# OLED_Adapter.net
KiCad netlist of a schematic drawn in EAGLE
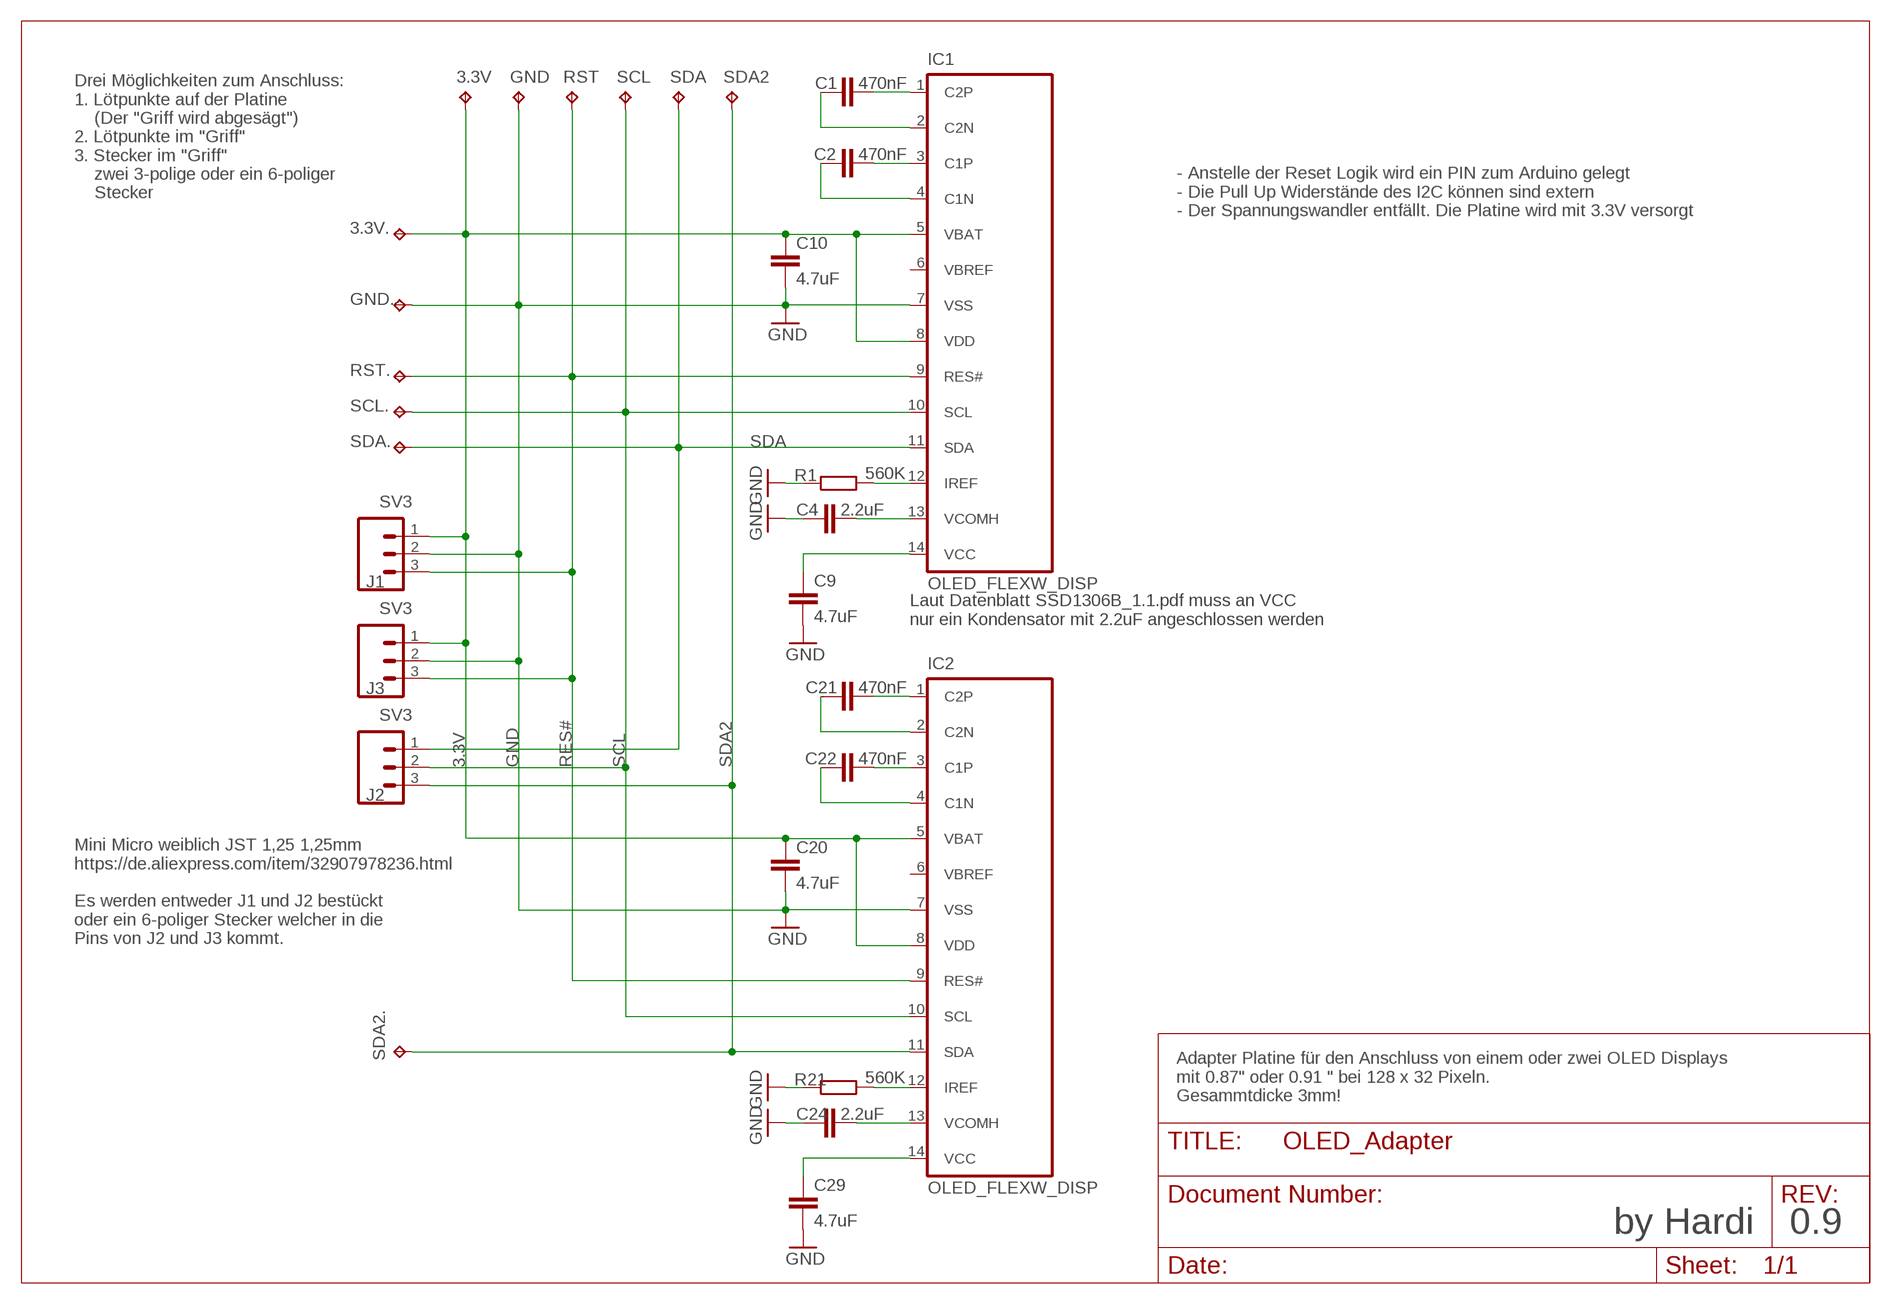
[diagram p0: schematic, sheet 1]

(export (version "E")
  (design (tool "Eeschema 10.0.6"))
  (components
    (comp (ref "3.3V")
      (value "3.3V")
      (footprint "eagle-import:TP16SQ")
      (libsource (lib "eagle-import") (part "TPTP16SQ"))
    )
    (comp (ref "3.3V.")
      (value "TPTP16SQ")
      (footprint "eagle-import:TP16SQ")
      (libsource (lib "eagle-import") (part "TPTP16SQ"))
    )
    (comp (ref "C1")
      (value "470nF")
      (footprint "eagle-import:C0603")
      (libsource (lib "eagle-import") (part "C-EUC0603"))
    )
    (comp (ref "C2")
      (value "470nF")
      (footprint "eagle-import:C0603")
      (libsource (lib "eagle-import") (part "C-EUC0603"))
    )
    (comp (ref "C4")
      (value "2.2uF")
      (footprint "eagle-import:C0603")
      (libsource (lib "eagle-import") (part "C-EUC0603"))
    )
    (comp (ref "C9")
      (value "4.7uF")
      (footprint "eagle-import:C0603")
      (libsource (lib "eagle-import") (part "C-EUC0603"))
    )
    (comp (ref "C10")
      (value "4.7uF")
      (footprint "eagle-import:C0603")
      (libsource (lib "eagle-import") (part "C-EUC0603"))
    )
    (comp (ref "C20")
      (value "4.7uF")
      (footprint "eagle-import:C0603")
      (libsource (lib "eagle-import") (part "C-EUC0603"))
    )
    (comp (ref "C21")
      (value "470nF")
      (footprint "eagle-import:C0603")
      (libsource (lib "eagle-import") (part "C-EUC0603"))
    )
    (comp (ref "C22")
      (value "470nF")
      (footprint "eagle-import:C0603")
      (libsource (lib "eagle-import") (part "C-EUC0603"))
    )
    (comp (ref "C24")
      (value "2.2uF")
      (footprint "eagle-import:C0603")
      (libsource (lib "eagle-import") (part "C-EUC0603"))
    )
    (comp (ref "C29")
      (value "4.7uF")
      (footprint "eagle-import:C0603")
      (libsource (lib "eagle-import") (part "C-EUC0603"))
    )
    (comp (ref "GND")
      (value "GND")
      (footprint "eagle-import:TP16R")
      (libsource (lib "eagle-import") (part "TPTP16R"))
    )
    (comp (ref "GND.")
      (value "TPTP16R")
      (footprint "eagle-import:TP16R")
      (libsource (lib "eagle-import") (part "TPTP16R"))
    )
    (comp (ref "IC1")
      (value "OLED_FLEXW_DISP")
      (footprint "eagle-import:OLED_FLEX_W_DISP")
      (libsource (lib "eagle-import") (part "OLED_FLEXW_DISP"))
    )
    (comp (ref "IC2")
      (value "OLED_FLEXW_DISP")
      (footprint "eagle-import:OLED_FLEX_W_DISP")
      (libsource (lib "eagle-import") (part "OLED_FLEXW_DISP"))
    )
    (comp (ref "J1")
      (value "SV3")
      (footprint "eagle-import:MINI")
      (libsource (lib "eagle-import") (part "M03"))
    )
    (comp (ref "J2")
      (value "SV3")
      (footprint "eagle-import:MINI")
      (libsource (lib "eagle-import") (part "M03"))
    )
    (comp (ref "J3")
      (value "SV3")
      (footprint "eagle-import:MINI")
      (libsource (lib "eagle-import") (part "M03"))
    )
    (comp (ref "R1")
      (value "560K")
      (footprint "eagle-import:R0603")
      (libsource (lib "eagle-import") (part "R-EU_R0603"))
    )
    (comp (ref "R21")
      (value "560K")
      (footprint "eagle-import:R0603")
      (libsource (lib "eagle-import") (part "R-EU_R0603"))
    )
    (comp (ref "RST")
      (value "RST")
      (footprint "eagle-import:TP16R")
      (libsource (lib "eagle-import") (part "TPTP16R"))
    )
    (comp (ref "RST.")
      (value "TPTP16R")
      (footprint "eagle-import:TP16R")
      (libsource (lib "eagle-import") (part "TPTP16R"))
    )
    (comp (ref "SCL")
      (value "SCL")
      (footprint "eagle-import:TP16R")
      (libsource (lib "eagle-import") (part "TPTP16R"))
    )
    (comp (ref "SCL.")
      (value "TPTP16R")
      (footprint "eagle-import:TP16R")
      (libsource (lib "eagle-import") (part "TPTP16R"))
    )
    (comp (ref "SDA")
      (value "SDA")
      (footprint "eagle-import:TP16R")
      (libsource (lib "eagle-import") (part "TPTP16R"))
    )
    (comp (ref "SDA.")
      (value "TPTP16R")
      (footprint "eagle-import:TP16R")
      (libsource (lib "eagle-import") (part "TPTP16R"))
    )
    (comp (ref "SDA2")
      (value "SDA2")
      (footprint "eagle-import:TP16R")
      (libsource (lib "eagle-import") (part "TPTP16R"))
    )
    (comp (ref "SDA2.")
      (value "TPTP16R")
      (footprint "eagle-import:TP16R")
      (libsource (lib "eagle-import") (part "TPTP16R"))
    )
  )
  (nets
    (net (code "1") (name "/3.3V") (class "Default")
      (node (ref "3.3V") (pin "TP") (pinfunction "TP_TP") (pintype "input"))
      (node (ref "3.3V.") (pin "TP") (pinfunction "TP_TP") (pintype "input"))
      (node (ref "C10") (pin "1") (pinfunction "1_1") (pintype "passive"))
      (node (ref "C20") (pin "1") (pinfunction "1_1") (pintype "passive"))
      (node (ref "IC1") (pin "5") (pinfunction "VBAT_5") (pintype "power_in"))
      (node (ref "IC1") (pin "8") (pinfunction "VDD_8") (pintype "power_in"))
      (node (ref "IC2") (pin "5") (pinfunction "VBAT_5") (pintype "power_in"))
      (node (ref "IC2") (pin "8") (pinfunction "VDD_8") (pintype "power_in"))
      (node (ref "J1") (pin "1") (pinfunction "1_1") (pintype "passive"))
      (node (ref "J3") (pin "1") (pinfunction "1_1") (pintype "passive"))
    )
    (net (code "2") (name "/RES#") (class "Default")
      (node (ref "IC1") (pin "9") (pinfunction "RES#_9") (pintype "input"))
      (node (ref "IC2") (pin "9") (pinfunction "RES#_9") (pintype "input"))
      (node (ref "J1") (pin "3") (pinfunction "3_3") (pintype "passive"))
      (node (ref "J3") (pin "3") (pinfunction "3_3") (pintype "passive"))
      (node (ref "RST") (pin "TP") (pinfunction "TP_TP") (pintype "input"))
      (node (ref "RST.") (pin "TP") (pinfunction "TP_TP") (pintype "input"))
    )
    (net (code "3") (name "/SCL") (class "Default")
      (node (ref "IC1") (pin "10") (pinfunction "SCL_10") (pintype "bidirectional"))
      (node (ref "IC2") (pin "10") (pinfunction "SCL_10") (pintype "bidirectional"))
      (node (ref "J2") (pin "2") (pinfunction "2_2") (pintype "passive"))
      (node (ref "SCL") (pin "TP") (pinfunction "TP_TP") (pintype "input"))
      (node (ref "SCL.") (pin "TP") (pinfunction "TP_TP") (pintype "input"))
    )
    (net (code "4") (name "/SDA") (class "Default")
      (node (ref "IC1") (pin "11") (pinfunction "SDA_11") (pintype "bidirectional"))
      (node (ref "J2") (pin "1") (pinfunction "1_1") (pintype "passive"))
      (node (ref "SDA") (pin "TP") (pinfunction "TP_TP") (pintype "input"))
      (node (ref "SDA.") (pin "TP") (pinfunction "TP_TP") (pintype "input"))
    )
    (net (code "5") (name "/SDA2") (class "Default")
      (node (ref "IC2") (pin "11") (pinfunction "SDA_11") (pintype "bidirectional"))
      (node (ref "J2") (pin "3") (pinfunction "3_3") (pintype "passive"))
      (node (ref "SDA2") (pin "TP") (pinfunction "TP_TP") (pintype "input"))
      (node (ref "SDA2.") (pin "TP") (pinfunction "TP_TP") (pintype "input"))
    )
    (net (code "6") (name "GND") (class "Default")
      (node (ref "C10") (pin "2") (pinfunction "2_2") (pintype "passive"))
      (node (ref "C20") (pin "2") (pinfunction "2_2") (pintype "passive"))
      (node (ref "C24") (pin "1") (pinfunction "1_1") (pintype "passive"))
      (node (ref "C29") (pin "2") (pinfunction "2_2") (pintype "passive"))
      (node (ref "C4") (pin "1") (pinfunction "1_1") (pintype "passive"))
      (node (ref "C9") (pin "2") (pinfunction "2_2") (pintype "passive"))
      (node (ref "GND") (pin "TP") (pinfunction "TP_TP") (pintype "input"))
      (node (ref "GND.") (pin "TP") (pinfunction "TP_TP") (pintype "input"))
      (node (ref "IC1") (pin "7") (pinfunction "VSS_7") (pintype "power_in"))
      (node (ref "IC2") (pin "7") (pinfunction "VSS_7") (pintype "power_in"))
      (node (ref "J1") (pin "2") (pinfunction "2_2") (pintype "passive"))
      (node (ref "J3") (pin "2") (pinfunction "2_2") (pintype "passive"))
      (node (ref "R1") (pin "1") (pinfunction "1_1") (pintype "passive"))
      (node (ref "R21") (pin "1") (pinfunction "1_1") (pintype "passive"))
    )
    (net (code "7") (name "Net-(IC1-C1N)") (class "Default")
      (node (ref "C2") (pin "1") (pinfunction "1_1") (pintype "passive"))
      (node (ref "IC1") (pin "4") (pinfunction "C1N_4") (pintype "bidirectional"))
    )
    (net (code "8") (name "Net-(IC1-C1P)") (class "Default")
      (node (ref "C2") (pin "2") (pinfunction "2_2") (pintype "passive"))
      (node (ref "IC1") (pin "3") (pinfunction "C1P_3") (pintype "bidirectional"))
    )
    (net (code "9") (name "Net-(IC1-C2N)") (class "Default")
      (node (ref "C1") (pin "1") (pinfunction "1_1") (pintype "passive"))
      (node (ref "IC1") (pin "2") (pinfunction "C2N_2") (pintype "bidirectional"))
    )
    (net (code "10") (name "Net-(IC1-C2P)") (class "Default")
      (node (ref "C1") (pin "2") (pinfunction "2_2") (pintype "passive"))
      (node (ref "IC1") (pin "1") (pinfunction "C2P_1") (pintype "bidirectional"))
    )
    (net (code "11") (name "Net-(IC1-IREF)") (class "Default")
      (node (ref "IC1") (pin "12") (pinfunction "IREF_12") (pintype "input"))
      (node (ref "R1") (pin "2") (pinfunction "2_2") (pintype "passive"))
    )
    (net (code "12") (name "Net-(IC1-VCC)") (class "Default")
      (node (ref "C9") (pin "1") (pinfunction "1_1") (pintype "passive"))
      (node (ref "IC1") (pin "14") (pinfunction "VCC_14") (pintype "power_in"))
    )
    (net (code "13") (name "Net-(IC1-VCOMH)") (class "Default")
      (node (ref "C4") (pin "2") (pinfunction "2_2") (pintype "passive"))
      (node (ref "IC1") (pin "13") (pinfunction "VCOMH_13") (pintype "input"))
    )
    (net (code "14") (name "Net-(IC2-C1N)") (class "Default")
      (node (ref "C22") (pin "1") (pinfunction "1_1") (pintype "passive"))
      (node (ref "IC2") (pin "4") (pinfunction "C1N_4") (pintype "bidirectional"))
    )
    (net (code "15") (name "Net-(IC2-C1P)") (class "Default")
      (node (ref "C22") (pin "2") (pinfunction "2_2") (pintype "passive"))
      (node (ref "IC2") (pin "3") (pinfunction "C1P_3") (pintype "bidirectional"))
    )
    (net (code "16") (name "Net-(IC2-C2N)") (class "Default")
      (node (ref "C21") (pin "1") (pinfunction "1_1") (pintype "passive"))
      (node (ref "IC2") (pin "2") (pinfunction "C2N_2") (pintype "bidirectional"))
    )
    (net (code "17") (name "Net-(IC2-C2P)") (class "Default")
      (node (ref "C21") (pin "2") (pinfunction "2_2") (pintype "passive"))
      (node (ref "IC2") (pin "1") (pinfunction "C2P_1") (pintype "bidirectional"))
    )
    (net (code "18") (name "Net-(IC2-IREF)") (class "Default")
      (node (ref "IC2") (pin "12") (pinfunction "IREF_12") (pintype "input"))
      (node (ref "R21") (pin "2") (pinfunction "2_2") (pintype "passive"))
    )
    (net (code "19") (name "Net-(IC2-VCC)") (class "Default")
      (node (ref "C29") (pin "1") (pinfunction "1_1") (pintype "passive"))
      (node (ref "IC2") (pin "14") (pinfunction "VCC_14") (pintype "power_in"))
    )
    (net (code "20") (name "Net-(IC2-VCOMH)") (class "Default")
      (node (ref "C24") (pin "2") (pinfunction "2_2") (pintype "passive"))
      (node (ref "IC2") (pin "13") (pinfunction "VCOMH_13") (pintype "input"))
    )
    (net (code "21") (name "unconnected-(IC1-VBREF-Pad6)") (class "Default")
      (node (ref "IC1") (pin "6") (pinfunction "VBREF_6") (pintype "input"))
    )
    (net (code "22") (name "unconnected-(IC2-VBREF-Pad6)") (class "Default")
      (node (ref "IC2") (pin "6") (pinfunction "VBREF_6") (pintype "input"))
    )
  )
)
